# 12-DPLL-01.net
KiCad netlist of a schematic drawn in Altium Designer
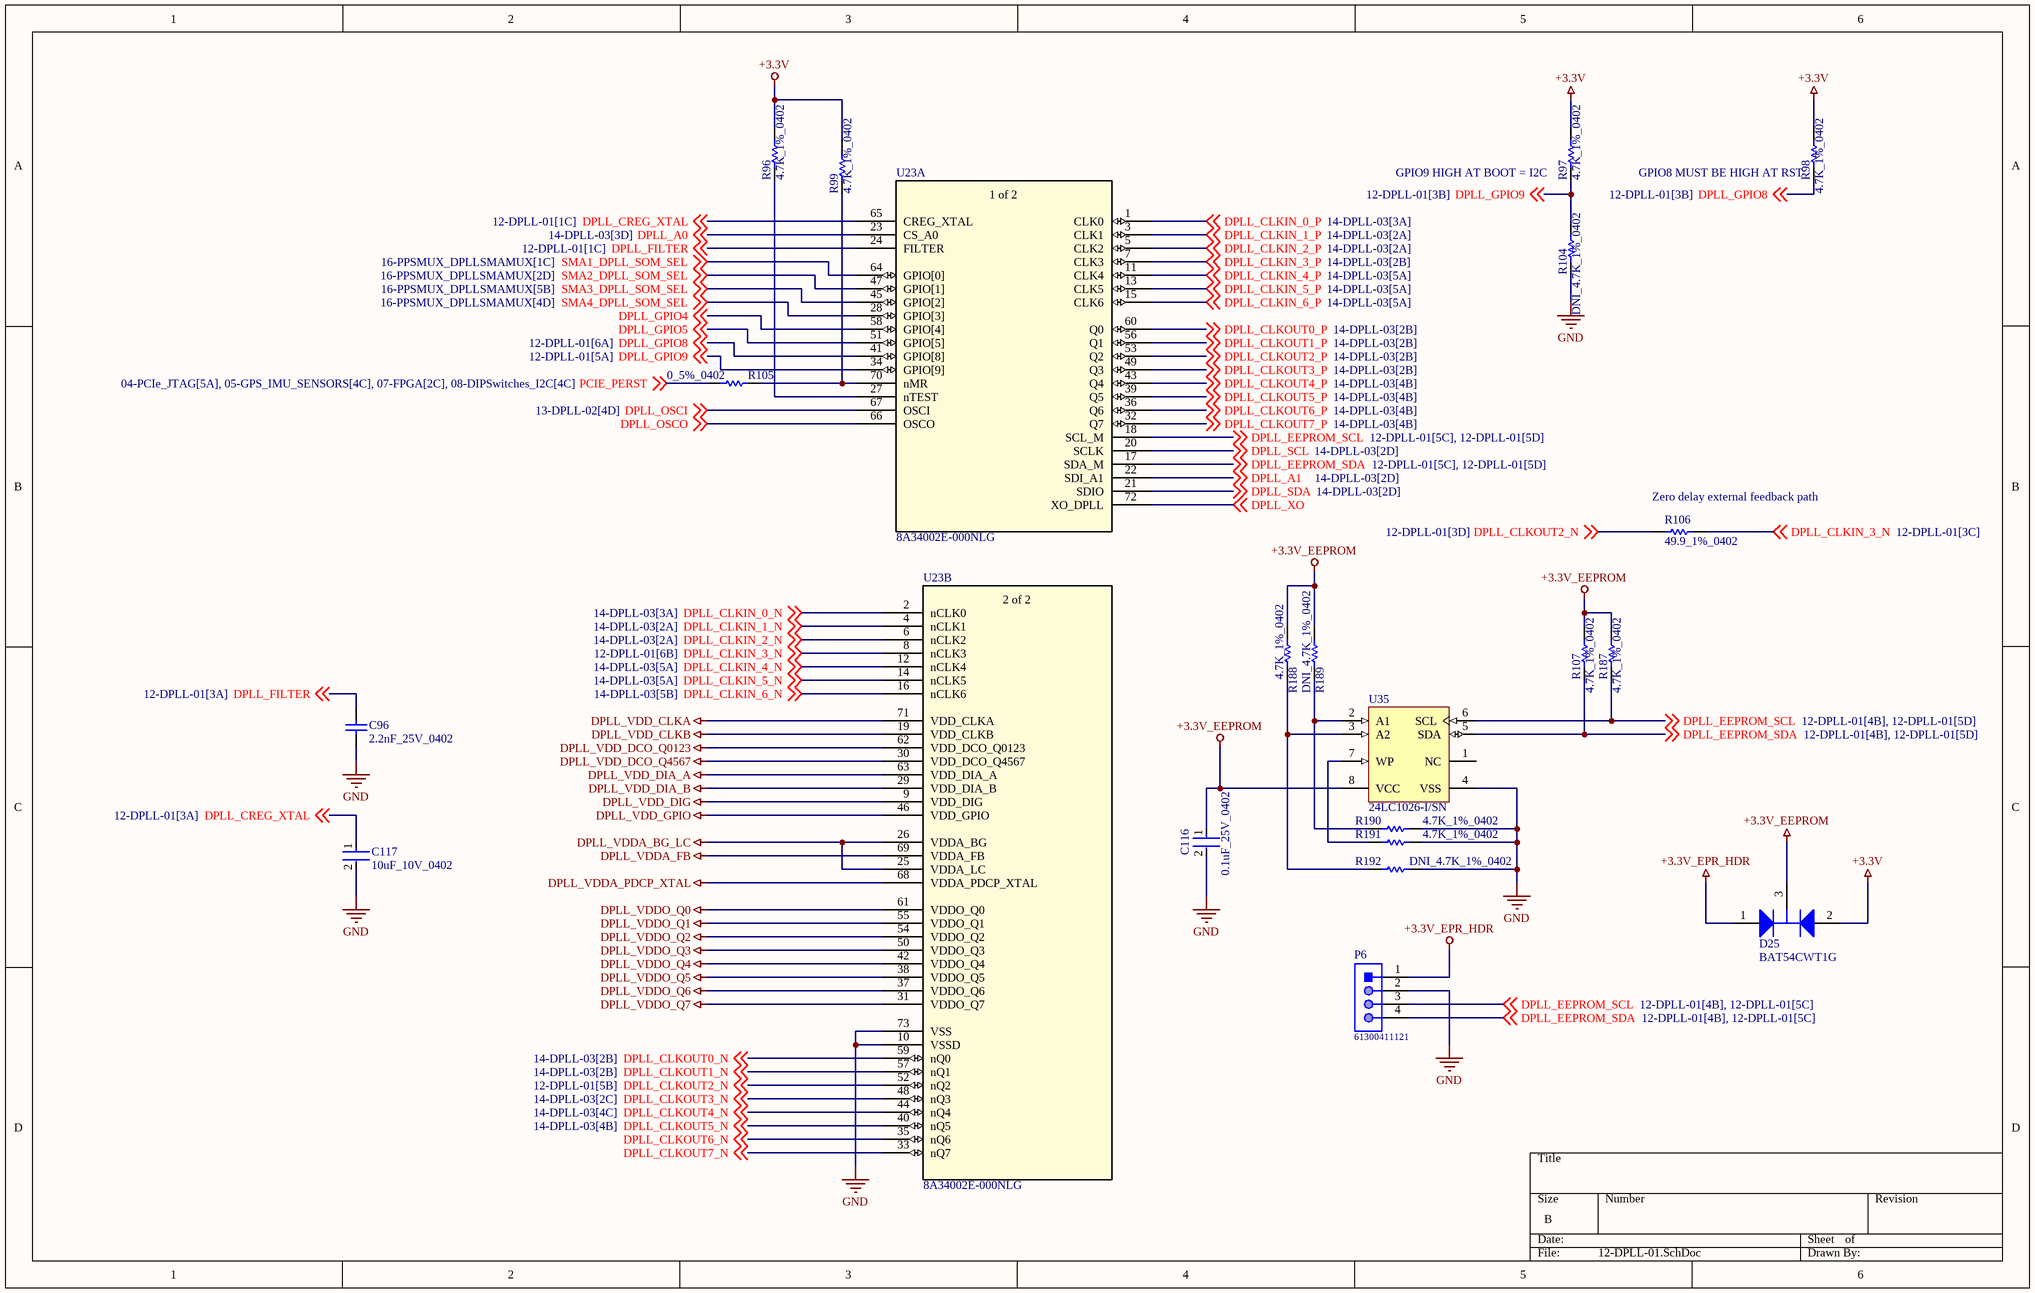
[diagram p0: 12-DPLL-01.SchDoc]

(export (version "E")
  (design (tool "Eeschema 10.0.6"))
  (components
    (comp (ref "C96")
      (value "2.2nF_25V_0402")
      (footprint "CAPC1005X56X25LL10T15")
      (fields
        (field (name "MANUFACTURER") "AVX Interconnect / Elco")
        (field (name "PART NUMBER") "04025C222JAT2A")
      )
      (libsource (lib "Altium Content Vault") (part "CAP"))
    )
    (comp (ref "C116")
      (value "0.1uF_25V_0402")
      (footprint "FP-0402-L_1_0_1-W_0_5_0_1-IPC_C")
      (description "General Purpose Ceramic Capacitor, 0402, 100nF, 10%, X7R, 15%, 25V")
      (fields (field (name "VOLTAGE") "25V") (field (name "TOLERANCE") "10%"))
      (libsource (lib "Altium Content Vault") (part "b4654b650e69147ec39a6b967a45e02"))
    )
    (comp (ref "C117")
      (value "10uF_10V_0402")
      (footprint "FP-CL05A106MP5NUNC-MFG")
      (description "CAP CER 10UF 10V X5R 0402")
      (fields
        (field (name "OCTOPART") "https://octopart.com/cl05a106mp5nunc-samsung-22457395")
        (field (name "TOLERANCE") "20%")
      )
      (libsource (lib "Altium Content Vault") (part "b4654b650e69147ec39a6b967a45e02"))
    )
    (comp (ref "D25")
      (value "BAT54CWT1G")
      (footprint "ONSC-SOT-323-3-419-04_V")
      (description "Dual Series Cathode Schottky Barrier Diodes, 3-Pin SOT-323, Pb-Free, Tape and Reel")
      (fields (field (name "MANUFACTURER") "On Semiconductor"))
      (libsource (lib "Altium Content Vault") (part "ONSC-D-A1A2K3-3"))
    )
    (comp (ref "P6")
      (value "61300411121")
      (footprint "61300411121")
      (description "THT Vertical Pin Header WR-PHD, Pitch 2.54 mm, Single Row, 4 pins")
      (fields (field (name "MANUFACTURER") "Wurth Elektronik") (field (name "PUBLISHER") "WurthElektronik"))
      (libsource (lib "Altium Content Vault") (part "WE-CN-1P-M-R4"))
    )
    (comp (ref "R96")
      (value "4.7K_1%_0402")
      (footprint "RESC1005X40X25NL10T10")
      (fields (field (name "MANUFACTURER") "Bourns") (field (name "PART NUMBER") "CR0402-FX-4701GLF"))
      (libsource (lib "Altium Content Vault") (part "RES"))
    )
    (comp (ref "R97")
      (value "4.7K_1%_0402")
      (footprint "RESC1005X40X25NL10T10")
      (fields (field (name "MANUFACTURER") "Bourns") (field (name "PART NUMBER") "CR0402-FX-4701GLF"))
      (libsource (lib "Altium Content Vault") (part "RES"))
    )
    (comp (ref "R98")
      (value "4.7K_1%_0402")
      (footprint "RESC1005X40X25NL10T10")
      (fields (field (name "MANUFACTURER") "Bourns") (field (name "PART NUMBER") "CR0402-FX-4701GLF"))
      (libsource (lib "Altium Content Vault") (part "RES"))
    )
    (comp (ref "R99")
      (value "4.7K_1%_0402")
      (footprint "RESC1005X40X25NL10T10")
      (fields (field (name "MANUFACTURER") "Bourns") (field (name "PART NUMBER") "CR0402-FX-4701GLF"))
      (libsource (lib "Altium Content Vault") (part "RES"))
    )
    (comp (ref "R104")
      (value "DNI_4.7K_1%_0402")
      (footprint "RESC1005X40X25NL10T10")
      (fields (field (name "MANUFACTURER") "Bourns") (field (name "PART NUMBER") "CR0402-FX-4701GLF"))
      (libsource (lib "Altium Content Vault") (part "RES"))
    )
    (comp (ref "R105")
      (value "0_5%_0402")
      (footprint "RESC1005X40X25LL10T10")
      (fields (field (name "MANUFACTURER") "KOA Speer") (field (name "PART NUMBER") "RK73Z1ETTP"))
      (libsource (lib "Altium Content Vault") (part "RES"))
    )
    (comp (ref "R106")
      (value "49.9_1%_0402")
      (footprint "RESC1005X40X25NL10T10")
      (fields (field (name "PART NUMBER") "RK73H1ETTP49R9F") (field (name "MANUFACTURER") "KOA Speer"))
      (libsource (lib "Altium Content Vault") (part "RES"))
    )
    (comp (ref "R107")
      (value "4.7K_1%_0402")
      (footprint "RESC1005X40X25NL10T10")
      (fields (field (name "MANUFACTURER") "Bourns") (field (name "PART NUMBER") "CR0402-FX-4701GLF"))
      (libsource (lib "Altium Content Vault") (part "RES"))
    )
    (comp (ref "R187")
      (value "4.7K_1%_0402")
      (footprint "RESC1005X40X25NL10T10")
      (fields (field (name "MANUFACTURER") "Bourns") (field (name "PART NUMBER") "CR0402-FX-4701GLF"))
      (libsource (lib "Altium Content Vault") (part "RES"))
    )
    (comp (ref "R188")
      (value "4.7K_1%_0402")
      (footprint "RESC1005X40X25NL10T10")
      (fields (field (name "MANUFACTURER") "Bourns") (field (name "PART NUMBER") "CR0402-FX-4701GLF"))
      (libsource (lib "Altium Content Vault") (part "RES"))
    )
    (comp (ref "R189")
      (value "DNI_4.7K_1%_0402")
      (footprint "RESC1005X40X25NL10T10")
      (fields (field (name "MANUFACTURER") "Bourns") (field (name "PART NUMBER") "CR0402-FX-4701GLF"))
      (libsource (lib "Altium Content Vault") (part "RES"))
    )
    (comp (ref "R190")
      (value "4.7K_1%_0402")
      (footprint "RESC1005X40X25NL10T10")
      (fields (field (name "MANUFACTURER") "Bourns") (field (name "PART NUMBER") "CR0402-FX-4701GLF"))
      (libsource (lib "Altium Content Vault") (part "RES"))
    )
    (comp (ref "R191")
      (value "4.7K_1%_0402")
      (footprint "RESC1005X40X25NL10T10")
      (fields (field (name "MANUFACTURER") "Bourns") (field (name "PART NUMBER") "CR0402-FX-4701GLF"))
      (libsource (lib "Altium Content Vault") (part "RES"))
    )
    (comp (ref "R192")
      (value "DNI_4.7K_1%_0402")
      (footprint "RESC1005X40X25NL10T10")
      (fields (field (name "MANUFACTURER") "Bourns") (field (name "PART NUMBER") "CR0402-FX-4701GLF"))
      (libsource (lib "Altium Content Vault") (part "RES"))
    )
    (comp (ref "U23")
      (value "8A34002E-000NLG")
      (footprint "QFN_2E-000NLG_REN")
      (description "No Description Available")
      (libsource (lib "8A34002E-000NLG") (part "8A34002E-000NLG"))
    )
    (comp (ref "U35")
      (value "24LC1026-I/SN")
      (footprint "MCHP-SOIC-SN8_N")
      (description "1024K bits I2C™ Serial EEPROM, 2.5 to 5.5 V, 400 kHz, -40 to 85 degC, 8-pin SOIC (SN8), Tube")
      (fields (field (name "MANUFACTURER") "Microchip"))
      (libsource (lib "Altium Content Vault") (part "MCHP-24LC1026-SOIC-8"))
    )
  )
  (nets
    (net (code "1") (name "+3.3V") (class "Default")
      (node (ref "D25") (pin "2") (pinfunction "A2_2") (pintype "passive"))
      (node (ref "R96") (pin "2") (pinfunction "2_2") (pintype "passive"))
      (node (ref "R97") (pin "1") (pinfunction "1_1") (pintype "passive"))
      (node (ref "R98") (pin "1") (pinfunction "1_1") (pintype "passive"))
      (node (ref "R99") (pin "2") (pinfunction "2_2") (pintype "passive"))
    )
    (net (code "2") (name "+3.3V_EEPROM") (class "Default")
      (node (ref "C116") (pin "1") (pinfunction "1_1") (pintype "passive"))
      (node (ref "D25") (pin "3") (pinfunction "K_3") (pintype "passive"))
      (node (ref "R107") (pin "1") (pinfunction "1_1") (pintype "passive"))
      (node (ref "R187") (pin "1") (pinfunction "1_1") (pintype "passive"))
      (node (ref "R188") (pin "2") (pinfunction "2_2") (pintype "passive"))
      (node (ref "R189") (pin "2") (pinfunction "2_2") (pintype "passive"))
      (node (ref "U35") (pin "8") (pinfunction "VCC_8") (pintype "power_in"))
    )
    (net (code "3") (name "+3.3V_EPR_HDR") (class "Default")
      (node (ref "D25") (pin "1") (pinfunction "A1_1") (pintype "passive"))
      (node (ref "P6") (pin "1") (pinfunction "1_1") (pintype "passive"))
    )
    (net (code "4") (name "DPLL_A0") (class "Default")
      (node (ref "U23") (pin "23") (pinfunction "CS_A0_23") (pintype "passive"))
    )
    (net (code "5") (name "DPLL_A1") (class "Default")
      (node (ref "U23") (pin "22") (pinfunction "SDI_A1_22") (pintype "passive"))
    )
    (net (code "6") (name "DPLL_CLKIN_0_N") (class "Default")
      (node (ref "U23") (pin "2") (pinfunction "nCLK0_2") (pintype "passive"))
    )
    (net (code "7") (name "DPLL_CLKIN_0_P") (class "Default")
      (node (ref "U23") (pin "1") (pinfunction "CLK0_1") (pintype "bidirectional"))
    )
    (net (code "8") (name "DPLL_CLKIN_1_N") (class "Default")
      (node (ref "U23") (pin "4") (pinfunction "nCLK1_4") (pintype "passive"))
    )
    (net (code "9") (name "DPLL_CLKIN_1_P") (class "Default")
      (node (ref "U23") (pin "3") (pinfunction "CLK1_3") (pintype "bidirectional"))
    )
    (net (code "10") (name "DPLL_CLKIN_2_N") (class "Default")
      (node (ref "U23") (pin "6") (pinfunction "nCLK2_6") (pintype "passive"))
    )
    (net (code "11") (name "DPLL_CLKIN_2_P") (class "Default")
      (node (ref "U23") (pin "5") (pinfunction "CLK2_5") (pintype "bidirectional"))
    )
    (net (code "12") (name "DPLL_CLKIN_3_N") (class "Default")
      (node (ref "R106") (pin "2") (pinfunction "2_2") (pintype "passive"))
      (node (ref "U23") (pin "8") (pinfunction "nCLK3_8") (pintype "passive"))
    )
    (net (code "13") (name "DPLL_CLKIN_3_P") (class "Default")
      (node (ref "U23") (pin "7") (pinfunction "CLK3_7") (pintype "bidirectional"))
    )
    (net (code "14") (name "DPLL_CLKIN_4_N") (class "Default")
      (node (ref "U23") (pin "12") (pinfunction "nCLK4_12") (pintype "passive"))
    )
    (net (code "15") (name "DPLL_CLKIN_4_P") (class "Default")
      (node (ref "U23") (pin "11") (pinfunction "CLK4_11") (pintype "bidirectional"))
    )
    (net (code "16") (name "DPLL_CLKIN_5_N") (class "Default")
      (node (ref "U23") (pin "14") (pinfunction "nCLK5_14") (pintype "passive"))
    )
    (net (code "17") (name "DPLL_CLKIN_5_P") (class "Default")
      (node (ref "U23") (pin "13") (pinfunction "CLK5_13") (pintype "bidirectional"))
    )
    (net (code "18") (name "DPLL_CLKIN_6_N") (class "Default")
      (node (ref "U23") (pin "16") (pinfunction "nCLK6_16") (pintype "passive"))
    )
    (net (code "19") (name "DPLL_CLKIN_6_P") (class "Default")
      (node (ref "U23") (pin "15") (pinfunction "CLK6_15") (pintype "bidirectional"))
    )
    (net (code "20") (name "DPLL_CLKOUT0_N") (class "Default")
      (node (ref "U23") (pin "59") (pinfunction "nQ0_59") (pintype "bidirectional"))
    )
    (net (code "21") (name "DPLL_CLKOUT0_P") (class "Default")
      (node (ref "U23") (pin "60") (pinfunction "Q0_60") (pintype "bidirectional"))
    )
    (net (code "22") (name "DPLL_CLKOUT1_N") (class "Default")
      (node (ref "U23") (pin "57") (pinfunction "nQ1_57") (pintype "bidirectional"))
    )
    (net (code "23") (name "DPLL_CLKOUT1_P") (class "Default")
      (node (ref "U23") (pin "56") (pinfunction "Q1_56") (pintype "bidirectional"))
    )
    (net (code "24") (name "DPLL_CLKOUT2_N") (class "Default")
      (node (ref "R106") (pin "1") (pinfunction "1_1") (pintype "passive"))
      (node (ref "U23") (pin "52") (pinfunction "nQ2_52") (pintype "bidirectional"))
    )
    (net (code "25") (name "DPLL_CLKOUT2_P") (class "Default")
      (node (ref "U23") (pin "53") (pinfunction "Q2_53") (pintype "bidirectional"))
    )
    (net (code "26") (name "DPLL_CLKOUT3_N") (class "Default")
      (node (ref "U23") (pin "48") (pinfunction "nQ3_48") (pintype "bidirectional"))
    )
    (net (code "27") (name "DPLL_CLKOUT3_P") (class "Default")
      (node (ref "U23") (pin "49") (pinfunction "Q3_49") (pintype "bidirectional"))
    )
    (net (code "28") (name "DPLL_CLKOUT4_N") (class "Default")
      (node (ref "U23") (pin "44") (pinfunction "nQ4_44") (pintype "bidirectional"))
    )
    (net (code "29") (name "DPLL_CLKOUT4_P") (class "Default")
      (node (ref "U23") (pin "43") (pinfunction "Q4_43") (pintype "bidirectional"))
    )
    (net (code "30") (name "DPLL_CLKOUT5_N") (class "Default")
      (node (ref "U23") (pin "40") (pinfunction "nQ5_40") (pintype "bidirectional"))
    )
    (net (code "31") (name "DPLL_CLKOUT5_P") (class "Default")
      (node (ref "U23") (pin "39") (pinfunction "Q5_39") (pintype "bidirectional"))
    )
    (net (code "32") (name "DPLL_CLKOUT6_N") (class "Default")
      (node (ref "U23") (pin "35") (pinfunction "nQ6_35") (pintype "bidirectional"))
    )
    (net (code "33") (name "DPLL_CLKOUT6_P") (class "Default")
      (node (ref "U23") (pin "36") (pinfunction "Q6_36") (pintype "bidirectional"))
    )
    (net (code "34") (name "DPLL_CLKOUT7_N") (class "Default")
      (node (ref "U23") (pin "33") (pinfunction "nQ7_33") (pintype "bidirectional"))
    )
    (net (code "35") (name "DPLL_CLKOUT7_P") (class "Default")
      (node (ref "U23") (pin "32") (pinfunction "Q7_32") (pintype "bidirectional"))
    )
    (net (code "36") (name "DPLL_CREG_XTAL") (class "Default")
      (node (ref "C117") (pin "1") (pinfunction "1_1") (pintype "passive"))
      (node (ref "U23") (pin "65") (pinfunction "CREG_XTAL_65") (pintype "passive"))
    )
    (net (code "37") (name "DPLL_EEPROM_SCL") (class "Default")
      (node (ref "P6") (pin "3") (pinfunction "3_3") (pintype "passive"))
      (node (ref "R187") (pin "2") (pinfunction "2_2") (pintype "passive"))
      (node (ref "U23") (pin "18") (pinfunction "SCL_M_18") (pintype "passive"))
      (node (ref "U35") (pin "6") (pinfunction "SCL_6") (pintype "input"))
    )
    (net (code "38") (name "DPLL_EEPROM_SDA") (class "Default")
      (node (ref "P6") (pin "4") (pinfunction "4_4") (pintype "passive"))
      (node (ref "R107") (pin "2") (pinfunction "2_2") (pintype "passive"))
      (node (ref "U23") (pin "17") (pinfunction "SDA_M_17") (pintype "passive"))
      (node (ref "U35") (pin "5") (pinfunction "SDA_5") (pintype "bidirectional"))
    )
    (net (code "39") (name "DPLL_FILTER") (class "Default")
      (node (ref "C96") (pin "2") (pinfunction "2_2") (pintype "passive"))
      (node (ref "U23") (pin "24") (pinfunction "FILTER_24") (pintype "passive"))
    )
    (net (code "40") (name "DPLL_GPIO4") (class "Default")
      (node (ref "U23") (pin "58") (pinfunction "GPIO[4]_58") (pintype "bidirectional"))
    )
    (net (code "41") (name "DPLL_GPIO5") (class "Default")
      (node (ref "U23") (pin "51") (pinfunction "GPIO[5]_51") (pintype "bidirectional"))
    )
    (net (code "42") (name "DPLL_GPIO8") (class "Default")
      (node (ref "R98") (pin "2") (pinfunction "2_2") (pintype "passive"))
      (node (ref "U23") (pin "41") (pinfunction "GPIO[8]_41") (pintype "bidirectional"))
    )
    (net (code "43") (name "DPLL_GPIO9") (class "Default")
      (node (ref "R104") (pin "1") (pinfunction "1_1") (pintype "passive"))
      (node (ref "R97") (pin "2") (pinfunction "2_2") (pintype "passive"))
      (node (ref "U23") (pin "34") (pinfunction "GPIO[9]_34") (pintype "bidirectional"))
    )
    (net (code "44") (name "DPLL_OSCI") (class "Default")
      (node (ref "U23") (pin "67") (pinfunction "OSCI_67") (pintype "passive"))
    )
    (net (code "45") (name "DPLL_OSCO") (class "Default")
      (node (ref "U23") (pin "66") (pinfunction "OSCO_66") (pintype "passive"))
    )
    (net (code "46") (name "DPLL_SCL") (class "Default")
      (node (ref "U23") (pin "20") (pinfunction "SCLK_20") (pintype "passive"))
    )
    (net (code "47") (name "DPLL_SDA") (class "Default")
      (node (ref "U23") (pin "21") (pinfunction "SDIO_21") (pintype "passive"))
    )
    (net (code "48") (name "DPLL_VDDA_BG_LC") (class "Default")
      (node (ref "U23") (pin "25") (pinfunction "VDDA_LC_25") (pintype "power_in"))
      (node (ref "U23") (pin "26") (pinfunction "VDDA_BG_26") (pintype "power_in"))
    )
    (net (code "49") (name "DPLL_VDDA_FB") (class "Default")
      (node (ref "U23") (pin "69") (pinfunction "VDDA_FB_69") (pintype "power_in"))
    )
    (net (code "50") (name "DPLL_VDDA_PDCP_XTAL") (class "Default")
      (node (ref "U23") (pin "68") (pinfunction "VDDA_PDCP_XTAL_68") (pintype "power_in"))
    )
    (net (code "51") (name "DPLL_VDDO_Q0") (class "Default")
      (node (ref "U23") (pin "61") (pinfunction "VDDO_Q0_61") (pintype "power_in"))
    )
    (net (code "52") (name "DPLL_VDDO_Q1") (class "Default")
      (node (ref "U23") (pin "55") (pinfunction "VDDO_Q1_55") (pintype "power_in"))
    )
    (net (code "53") (name "DPLL_VDDO_Q2") (class "Default")
      (node (ref "U23") (pin "54") (pinfunction "VDDO_Q2_54") (pintype "power_in"))
    )
    (net (code "54") (name "DPLL_VDDO_Q3") (class "Default")
      (node (ref "U23") (pin "50") (pinfunction "VDDO_Q3_50") (pintype "power_in"))
    )
    (net (code "55") (name "DPLL_VDDO_Q4") (class "Default")
      (node (ref "U23") (pin "42") (pinfunction "VDDO_Q4_42") (pintype "power_in"))
    )
    (net (code "56") (name "DPLL_VDDO_Q5") (class "Default")
      (node (ref "U23") (pin "38") (pinfunction "VDDO_Q5_38") (pintype "power_in"))
    )
    (net (code "57") (name "DPLL_VDDO_Q6") (class "Default")
      (node (ref "U23") (pin "37") (pinfunction "VDDO_Q6_37") (pintype "power_in"))
    )
    (net (code "58") (name "DPLL_VDDO_Q7") (class "Default")
      (node (ref "U23") (pin "31") (pinfunction "VDDO_Q7_31") (pintype "power_in"))
    )
    (net (code "59") (name "DPLL_VDD_CLKA") (class "Default")
      (node (ref "U23") (pin "71") (pinfunction "VDD_CLKA_71") (pintype "power_in"))
    )
    (net (code "60") (name "DPLL_VDD_CLKB") (class "Default")
      (node (ref "U23") (pin "19") (pinfunction "VDD_CLKB_19") (pintype "power_in"))
    )
    (net (code "61") (name "DPLL_VDD_DCO_Q0123") (class "Default")
      (node (ref "U23") (pin "62") (pinfunction "VDD_DCO_Q0123_62") (pintype "power_in"))
    )
    (net (code "62") (name "DPLL_VDD_DCO_Q4567") (class "Default")
      (node (ref "U23") (pin "30") (pinfunction "VDD_DCO_Q4567_30") (pintype "power_in"))
    )
    (net (code "63") (name "DPLL_VDD_DIA_A") (class "Default")
      (node (ref "U23") (pin "63") (pinfunction "VDD_DIA_A_63") (pintype "power_in"))
    )
    (net (code "64") (name "DPLL_VDD_DIA_B") (class "Default")
      (node (ref "U23") (pin "29") (pinfunction "VDD_DIA_B_29") (pintype "power_in"))
    )
    (net (code "65") (name "DPLL_VDD_DIG") (class "Default")
      (node (ref "U23") (pin "9") (pinfunction "VDD_DIG_9") (pintype "power_in"))
    )
    (net (code "66") (name "DPLL_VDD_GPIO") (class "Default")
      (node (ref "U23") (pin "46") (pinfunction "VDD_GPIO_46") (pintype "power_in"))
    )
    (net (code "67") (name "DPLL_XO") (class "Default")
      (node (ref "U23") (pin "72") (pinfunction "XO_DPLL_72") (pintype "passive"))
    )
    (net (code "68") (name "GND") (class "Default")
      (node (ref "C116") (pin "2") (pinfunction "2_2") (pintype "passive"))
      (node (ref "C117") (pin "2") (pinfunction "2_2") (pintype "passive"))
      (node (ref "C96") (pin "1") (pinfunction "1_1") (pintype "passive"))
      (node (ref "P6") (pin "2") (pinfunction "2_2") (pintype "passive"))
      (node (ref "R104") (pin "2") (pinfunction "2_2") (pintype "passive"))
      (node (ref "R190") (pin "1") (pinfunction "1_1") (pintype "passive"))
      (node (ref "R191") (pin "1") (pinfunction "1_1") (pintype "passive"))
      (node (ref "R192") (pin "2") (pinfunction "2_2") (pintype "passive"))
      (node (ref "U23") (pin "10") (pinfunction "VSSD_10") (pintype "power_in"))
      (node (ref "U23") (pin "73") (pinfunction "VSS_73") (pintype "power_in"))
      (node (ref "U35") (pin "4") (pinfunction "VSS_4") (pintype "power_in"))
    )
    (net (code "69") (name "Net-(U23A-nMR)") (class "Default")
      (node (ref "R105") (pin "2") (pinfunction "2_2") (pintype "passive"))
      (node (ref "R99") (pin "1") (pinfunction "1_1") (pintype "passive"))
      (node (ref "U23") (pin "70") (pinfunction "nMR_70") (pintype "passive"))
    )
    (net (code "70") (name "Net-(U23A-nTEST)") (class "Default")
      (node (ref "R96") (pin "1") (pinfunction "1_1") (pintype "passive"))
      (node (ref "U23") (pin "27") (pinfunction "nTEST_27") (pintype "passive"))
    )
    (net (code "71") (name "Net-(U35-A1)") (class "Default")
      (node (ref "R189") (pin "1") (pinfunction "1_1") (pintype "passive"))
      (node (ref "R190") (pin "2") (pinfunction "2_2") (pintype "passive"))
      (node (ref "U35") (pin "2") (pinfunction "A1_2") (pintype "input"))
    )
    (net (code "72") (name "Net-(U35-A2)") (class "Default")
      (node (ref "R188") (pin "1") (pinfunction "1_1") (pintype "passive"))
      (node (ref "R192") (pin "1") (pinfunction "1_1") (pintype "passive"))
      (node (ref "U35") (pin "3") (pinfunction "A2_3") (pintype "input"))
    )
    (net (code "73") (name "Net-(U35-WP)") (class "Default")
      (node (ref "R191") (pin "2") (pinfunction "2_2") (pintype "passive"))
      (node (ref "U35") (pin "7") (pinfunction "WP_7") (pintype "input"))
    )
    (net (code "74") (name "PCIE_PERST") (class "Default")
      (node (ref "R105") (pin "1") (pinfunction "1_1") (pintype "passive"))
    )
    (net (code "75") (name "SMA1_DPLL_SOM_SEL") (class "Default")
      (node (ref "U23") (pin "64") (pinfunction "GPIO[0]_64") (pintype "bidirectional"))
    )
    (net (code "76") (name "SMA2_DPLL_SOM_SEL") (class "Default")
      (node (ref "U23") (pin "47") (pinfunction "GPIO[1]_47") (pintype "bidirectional"))
    )
    (net (code "77") (name "SMA3_DPLL_SOM_SEL") (class "Default")
      (node (ref "U23") (pin "45") (pinfunction "GPIO[2]_45") (pintype "bidirectional"))
    )
    (net (code "78") (name "SMA4_DPLL_SOM_SEL") (class "Default")
      (node (ref "U23") (pin "28") (pinfunction "GPIO[3]_28") (pintype "bidirectional"))
    )
    (net (code "79") (name "unconnected-(U35-NC-Pad1)") (class "Default")
      (node (ref "U35") (pin "1") (pinfunction "NC_1") (pintype "passive"))
    )
  )
)
